# CC-S05-V00-MicrocontrollerPeripherals.net
KiCad netlist of a schematic drawn in Altium Designer
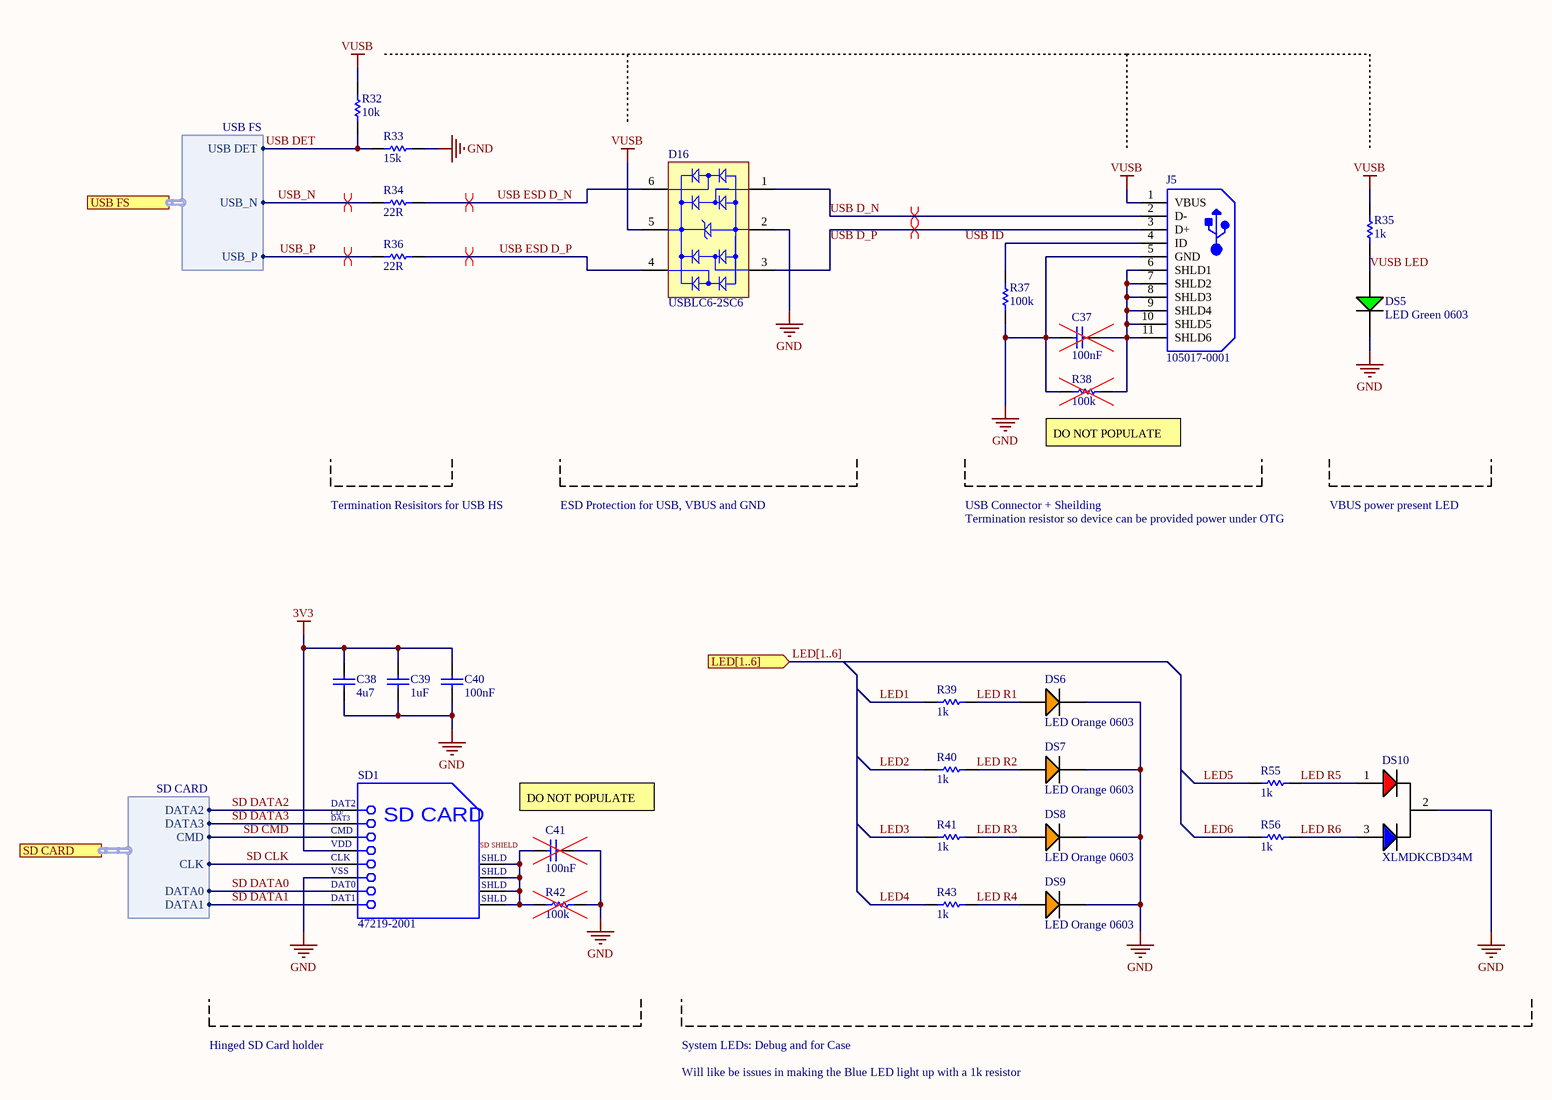
[diagram p0: CC-S05-V00-MicrocontrollerPeripherals.SchDoc]

(export (version "E")
  (design (tool "Eeschema 10.0.6"))
  (components
    (comp (ref "C37")
      (value "100nF")
      (footprint "Cap_Ceramic_0603")
      (description "Capacitor, Ceramic, SMD, 100nF, 50V, 5%, X7R, 0603")
      (libsource (lib "StandardCapacitors") (part "100nF 50V 5% X7R 0603"))
    )
    (comp (ref "C38")
      (value "4u7")
      (footprint "Cap_Ceramic_0603")
      (description "Capacitor, Ceramic, SMD, 4u7, 50V, 5%, X7R, 0603")
      (libsource (lib "StandardCapacitors") (part "4u7 50V 5% X7R 0603"))
    )
    (comp (ref "C39")
      (value "1uF")
      (footprint "Cap_Ceramic_0603")
      (description "Capacitor, Ceramic, SMD, 1uF, 25V, 5%, X7R, 0603")
      (libsource (lib "StandardCapacitors") (part "1uF 25V 5% X7R 0603"))
    )
    (comp (ref "C40")
      (value "100nF")
      (footprint "Cap_Ceramic_0603")
      (description "Capacitor, Ceramic, SMD, 100nF, 50V, 5%, X7R, 0603")
      (libsource (lib "StandardCapacitors") (part "100nF 50V 5% X7R 0603"))
    )
    (comp (ref "C41")
      (value "100nF")
      (footprint "Cap_Ceramic_0603")
      (description "Capacitor, Ceramic, SMD, 100nF, 50V, 5%, X7R, 0603")
      (libsource (lib "StandardCapacitors") (part "100nF 50V 5% X7R 0603"))
    )
    (comp (ref "D16")
      (value "USBLC6-2SC6")
      (footprint "USBLC6-2SC6")
      (description "Very low capacitance ESD protection, 3.5 pF, -40 to 125 degC, 6-Pin SOT23, RoHS, Tape and Reel")
      (libsource (lib "QUTMS_DiodeLibrary") (part "USBLC6-2SC6"))
    )
    (comp (ref "DS5")
      (value "LED Green 0603")
      (footprint "LED GREEN 0603")
      (libsource (lib "QUTMS_LEDLibrary") (part "LED Green 0603"))
    )
    (comp (ref "DS6")
      (value "LED Orange 0603")
      (footprint "LED ORANGE 0603")
      (libsource (lib "QUTMS_LEDLibrary") (part "LED Orange 0603"))
    )
    (comp (ref "DS7")
      (value "LED Orange 0603")
      (footprint "LED ORANGE 0603")
      (libsource (lib "QUTMS_LEDLibrary") (part "LED Orange 0603"))
    )
    (comp (ref "DS8")
      (value "LED Orange 0603")
      (footprint "LED ORANGE 0603")
      (libsource (lib "QUTMS_LEDLibrary") (part "LED Orange 0603"))
    )
    (comp (ref "DS9")
      (value "LED Orange 0603")
      (footprint "LED ORANGE 0603")
      (libsource (lib "QUTMS_LEDLibrary") (part "LED Orange 0603"))
    )
    (comp (ref "DS10")
      (value "XLMDKCBD34M")
      (footprint "XLxxxx34x")
      (description "Blue, Red 465nm Blue, 630nm Red LED Indication - Discrete 3.3V Blue, 1.95V Red Radial")
      (libsource (lib "QUTMS_LEDLibrary") (part "XLMDKCBD34M"))
    )
    (comp (ref "J5")
      (value "105017-0001")
      (footprint "105017-0001")
      (libsource (lib "QUTMS_PeripheralConnectivity") (part "105017-0001"))
    )
    (comp (ref "R32")
      (value "10k")
      (footprint "Res_ThinFilm_0603")
      (description "Resistor, SMD, 10k, 0.1W, 5%, 0603")
      (libsource (lib "StandardResistors") (part "10k 5% 0603"))
    )
    (comp (ref "R33")
      (value "15k")
      (footprint "Res_ThinFilm_0603")
      (description "Resistor, SMD, 15k, 0.1W, 5%, 0603")
      (libsource (lib "StandardResistors") (part "15k 5% 0603"))
    )
    (comp (ref "R34")
      (value "22R")
      (footprint "Res_ThinFilm_0603")
      (description "Resistor, SMD, 22R, 0.1W, 5%, 0603")
      (libsource (lib "StandardResistors") (part "22R 5% 0603"))
    )
    (comp (ref "R35")
      (value "1k")
      (footprint "Res_ThinFilm_0603")
      (description "Resistor, SMD, 1k, 0.1W, 5%, 0603")
      (libsource (lib "StandardResistors") (part "1k 5% 0603"))
    )
    (comp (ref "R36")
      (value "22R")
      (footprint "Res_ThinFilm_0603")
      (description "Resistor, SMD, 22R, 0.1W, 5%, 0603")
      (libsource (lib "StandardResistors") (part "22R 5% 0603"))
    )
    (comp (ref "R37")
      (value "100k")
      (footprint "Res_ThinFilm_0603")
      (description "Resistor, SMD, 100k, 0.1W, 5%, 0603")
      (libsource (lib "StandardResistors") (part "100k 5%, 0603"))
    )
    (comp (ref "R38")
      (value "100k")
      (footprint "Res_ThinFilm_0603")
      (description "Resistor, SMD, 100k, 0.1W, 5%, 0603")
      (libsource (lib "StandardResistors") (part "100k 5%, 0603"))
    )
    (comp (ref "R39")
      (value "1k")
      (footprint "Res_ThinFilm_0603")
      (description "Resistor, SMD, 1k, 0.1W, 5%, 0603")
      (libsource (lib "StandardResistors") (part "1k 5% 0603"))
    )
    (comp (ref "R40")
      (value "1k")
      (footprint "Res_ThinFilm_0603")
      (description "Resistor, SMD, 1k, 0.1W, 5%, 0603")
      (libsource (lib "StandardResistors") (part "1k 5% 0603"))
    )
    (comp (ref "R41")
      (value "1k")
      (footprint "Res_ThinFilm_0603")
      (description "Resistor, SMD, 1k, 0.1W, 5%, 0603")
      (libsource (lib "StandardResistors") (part "1k 5% 0603"))
    )
    (comp (ref "R42")
      (value "100k")
      (footprint "Res_ThinFilm_0603")
      (description "Resistor, SMD, 100k, 0.1W, 5%, 0603")
      (libsource (lib "StandardResistors") (part "100k 5%, 0603"))
    )
    (comp (ref "R43")
      (value "1k")
      (footprint "Res_ThinFilm_0603")
      (description "Resistor, SMD, 1k, 0.1W, 5%, 0603")
      (libsource (lib "StandardResistors") (part "1k 5% 0603"))
    )
    (comp (ref "R55")
      (value "1k")
      (footprint "Res_ThinFilm_0603")
      (description "Resistor, SMD, 1k, 0.1W, 5%, 0603")
      (libsource (lib "StandardResistors") (part "1k 5% 0603"))
    )
    (comp (ref "R56")
      (value "1k")
      (footprint "Res_ThinFilm_0603")
      (description "Resistor, SMD, 1k, 0.1W, 5%, 0603")
      (libsource (lib "StandardResistors") (part "1k 5% 0603"))
    )
    (comp (ref "SD1")
      (value "47219-2001")
      (footprint "47219-2001")
      (description "MicroSD Card Connector, Hinge Type, -40 to 85 degC, 8-Pin SMD, RoHS, Tape and Reel")
      (libsource (lib "QUTMS_PeripheralConnectivity") (part "47219-2001"))
    )
  )
  (nets
    (net (code "5") (name "/LED R1") (class "Default")
      (node (ref "DS6") (pin "1") (pinfunction "A_1") (pintype "passive"))
      (node (ref "R39") (pin "1") (pinfunction "1_1") (pintype "passive"))
    )
    (net (code "6") (name "/LED R2") (class "Default")
      (node (ref "DS7") (pin "1") (pinfunction "A_1") (pintype "passive"))
      (node (ref "R40") (pin "1") (pinfunction "1_1") (pintype "passive"))
    )
    (net (code "7") (name "/LED R3") (class "Default")
      (node (ref "DS8") (pin "1") (pinfunction "A_1") (pintype "passive"))
      (node (ref "R41") (pin "1") (pinfunction "1_1") (pintype "passive"))
    )
    (net (code "8") (name "/LED R4") (class "Default")
      (node (ref "DS9") (pin "1") (pinfunction "A_1") (pintype "passive"))
      (node (ref "R43") (pin "1") (pinfunction "1_1") (pintype "passive"))
    )
    (net (code "9") (name "/LED R5") (class "Default")
      (node (ref "DS10") (pin "1") (pinfunction "A_1") (pintype "passive"))
      (node (ref "R55") (pin "1") (pinfunction "1_1") (pintype "passive"))
    )
    (net (code "10") (name "/LED R6") (class "Default")
      (node (ref "DS10") (pin "3") (pinfunction "A_3") (pintype "passive"))
      (node (ref "R56") (pin "1") (pinfunction "1_1") (pintype "passive"))
    )
    (net (code "11") (name "/LED1") (class "Default")
      (node (ref "R39") (pin "2") (pinfunction "2_2") (pintype "passive"))
    )
    (net (code "12") (name "/LED2") (class "Default")
      (node (ref "R40") (pin "2") (pinfunction "2_2") (pintype "passive"))
    )
    (net (code "13") (name "/LED3") (class "Default")
      (node (ref "R41") (pin "2") (pinfunction "2_2") (pintype "passive"))
    )
    (net (code "14") (name "/LED4") (class "Default")
      (node (ref "R43") (pin "2") (pinfunction "2_2") (pintype "passive"))
    )
    (net (code "15") (name "/LED5") (class "Default")
      (node (ref "R55") (pin "2") (pinfunction "2_2") (pintype "passive"))
    )
    (net (code "16") (name "/LED6") (class "Default")
      (node (ref "R56") (pin "2") (pinfunction "2_2") (pintype "passive"))
    )
    (net (code "18") (name "/SD CLK") (class "Default")
      (node (ref "SD1") (pin "5") (pinfunction "CLK_5") (pintype "passive"))
    )
    (net (code "19") (name "/SD CMD") (class "Default")
      (node (ref "SD1") (pin "3") (pinfunction "CMD_3") (pintype "passive"))
    )
    (net (code "20") (name "/SD DATA0") (class "Default")
      (node (ref "SD1") (pin "7") (pinfunction "DAT0_7") (pintype "passive"))
    )
    (net (code "21") (name "/SD DATA1") (class "Default")
      (node (ref "SD1") (pin "8") (pinfunction "DAT1_8") (pintype "passive"))
    )
    (net (code "22") (name "/SD DATA2") (class "Default")
      (node (ref "SD1") (pin "1") (pinfunction "DAT2_1") (pintype "passive"))
    )
    (net (code "23") (name "/SD DATA3") (class "Default")
      (node (ref "SD1") (pin "2") (pinfunction "CD/DAT3_2") (pintype "passive"))
    )
    (net (code "24") (name "/SD SHIELD") (class "Default")
      (node (ref "C41") (pin "1") (pinfunction "1_1") (pintype "passive"))
      (node (ref "R42") (pin "2") (pinfunction "2_2") (pintype "passive"))
      (node (ref "SD1") (pin "10") (pinfunction "SHLD_10") (pintype "passive"))
      (node (ref "SD1") (pin "11") (pinfunction "SHLD_11") (pintype "passive"))
      (node (ref "SD1") (pin "12") (pinfunction "SHLD_12") (pintype "passive"))
      (node (ref "SD1") (pin "9") (pinfunction "SHLD_9") (pintype "passive"))
    )
    (net (code "25") (name "/USB DET") (class "Default")
      (node (ref "R32") (pin "1") (pinfunction "1_1") (pintype "passive"))
      (node (ref "R33") (pin "1") (pinfunction "1_1") (pintype "passive"))
    )
    (net (code "26") (name "/USB D_N") (class "Default")
      (node (ref "D16") (pin "1") (pinfunction "I/O_1_1") (pintype "passive"))
      (node (ref "J5") (pin "2") (pinfunction "D-_2") (pintype "passive"))
    )
    (net (code "27") (name "/USB D_P") (class "Default")
      (node (ref "D16") (pin "3") (pinfunction "I/O_2_3") (pintype "passive"))
      (node (ref "J5") (pin "3") (pinfunction "D+_3") (pintype "passive"))
    )
    (net (code "28") (name "/USB ESD D_N") (class "Default")
      (node (ref "D16") (pin "6") (pinfunction "I/O_4_6") (pintype "passive"))
      (node (ref "R34") (pin "2") (pinfunction "2_2") (pintype "passive"))
    )
    (net (code "29") (name "/USB ESD D_P") (class "Default")
      (node (ref "D16") (pin "4") (pinfunction "I/O_3_4") (pintype "passive"))
      (node (ref "R36") (pin "2") (pinfunction "2_2") (pintype "passive"))
    )
    (net (code "30") (name "/USB ID") (class "Default")
      (node (ref "J5") (pin "4") (pinfunction "ID_4") (pintype "passive"))
      (node (ref "R37") (pin "2") (pinfunction "2_2") (pintype "passive"))
    )
    (net (code "31") (name "/USB_N") (class "Default")
      (node (ref "R34") (pin "1") (pinfunction "1_1") (pintype "passive"))
    )
    (net (code "32") (name "/USB_P") (class "Default")
      (node (ref "R36") (pin "1") (pinfunction "1_1") (pintype "passive"))
    )
    (net (code "33") (name "/VUSB LED") (class "Default")
      (node (ref "DS5") (pin "1") (pinfunction "A_1") (pintype "passive"))
      (node (ref "R35") (pin "1") (pinfunction "1_1") (pintype "passive"))
    )
    (net (code "36") (name "3V3") (class "Default")
      (node (ref "C38") (pin "2") (pinfunction "2_2") (pintype "passive"))
      (node (ref "C39") (pin "2") (pinfunction "2_2") (pintype "passive"))
      (node (ref "C40") (pin "2") (pinfunction "2_2") (pintype "passive"))
      (node (ref "SD1") (pin "4") (pinfunction "VDD_4") (pintype "passive"))
    )
    (net (code "37") (name "GND") (class "Default")
      (node (ref "C37") (pin "1") (pinfunction "1_1") (pintype "passive"))
      (node (ref "C38") (pin "1") (pinfunction "1_1") (pintype "passive"))
      (node (ref "C39") (pin "1") (pinfunction "1_1") (pintype "passive"))
      (node (ref "C40") (pin "1") (pinfunction "1_1") (pintype "passive"))
      (node (ref "C41") (pin "2") (pinfunction "2_2") (pintype "passive"))
      (node (ref "D16") (pin "2") (pinfunction "GND_2") (pintype "passive"))
      (node (ref "DS10") (pin "2") (pinfunction "C_2") (pintype "passive"))
      (node (ref "DS5") (pin "2") (pinfunction "C_2") (pintype "passive"))
      (node (ref "DS6") (pin "2") (pinfunction "C_2") (pintype "passive"))
      (node (ref "DS7") (pin "2") (pinfunction "C_2") (pintype "passive"))
      (node (ref "DS8") (pin "2") (pinfunction "C_2") (pintype "passive"))
      (node (ref "DS9") (pin "2") (pinfunction "C_2") (pintype "passive"))
      (node (ref "J5") (pin "5") (pinfunction "GND_5") (pintype "passive"))
      (node (ref "R33") (pin "2") (pinfunction "2_2") (pintype "passive"))
      (node (ref "R37") (pin "1") (pinfunction "1_1") (pintype "passive"))
      (node (ref "R38") (pin "2") (pinfunction "2_2") (pintype "passive"))
      (node (ref "R42") (pin "1") (pinfunction "1_1") (pintype "passive"))
      (node (ref "SD1") (pin "6") (pinfunction "VSS_6") (pintype "passive"))
    )
    (net (code "38") (name "Net-(J5-SHLD1)") (class "Default")
      (node (ref "C37") (pin "2") (pinfunction "2_2") (pintype "passive"))
      (node (ref "J5") (pin "10") (pinfunction "SHLD5_10") (pintype "passive"))
      (node (ref "J5") (pin "11") (pinfunction "SHLD6_11") (pintype "passive"))
      (node (ref "J5") (pin "6") (pinfunction "SHLD1_6") (pintype "passive"))
      (node (ref "J5") (pin "7") (pinfunction "SHLD2_7") (pintype "passive"))
      (node (ref "J5") (pin "8") (pinfunction "SHLD3_8") (pintype "passive"))
      (node (ref "J5") (pin "9") (pinfunction "SHLD4_9") (pintype "passive"))
      (node (ref "R38") (pin "1") (pinfunction "1_1") (pintype "passive"))
    )
    (net (code "39") (name "VUSB") (class "Default")
      (node (ref "D16") (pin "5") (pinfunction "VBUS_5") (pintype "passive"))
      (node (ref "J5") (pin "1") (pinfunction "VBUS_1") (pintype "passive"))
      (node (ref "R32") (pin "2") (pinfunction "2_2") (pintype "passive"))
      (node (ref "R35") (pin "2") (pinfunction "2_2") (pintype "passive"))
    )
  )
)
